# Puzzle_I2C_hub.net
KiCad netlist of a schematic drawn in EAGLE
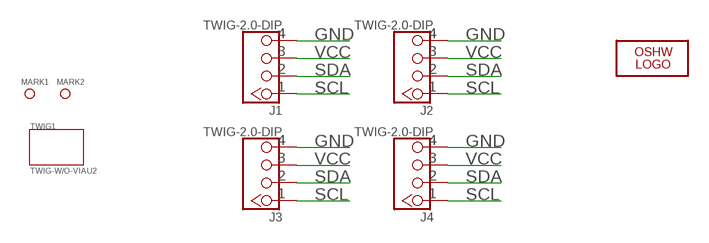
[diagram p0: schematic, sheet 1]

(export (version "E")
  (design (tool "Eeschema 10.0.6"))
  (components
    (comp (ref "J1")
      (value "TWIG-2.0-DIP")
      (footprint "eagle-import:2.0_1X4")
      (libsource (lib "eagle-import") (part "TWIG-2.0-DIP"))
    )
    (comp (ref "J2")
      (value "TWIG-2.0-DIP")
      (footprint "eagle-import:2.0_1X4")
      (libsource (lib "eagle-import") (part "TWIG-2.0-DIP"))
    )
    (comp (ref "J3")
      (value "TWIG-2.0-DIP")
      (footprint "eagle-import:2.0_1X4")
      (libsource (lib "eagle-import") (part "TWIG-2.0-DIP"))
    )
    (comp (ref "J4")
      (value "TWIG-2.0-DIP")
      (footprint "eagle-import:2.0_1X4")
      (libsource (lib "eagle-import") (part "TWIG-2.0-DIP"))
    )
    (comp (ref "LOGO3")
      (value "LOGO-OSHW-FILLX0150-NT")
      (footprint "eagle-import:OSHW_FILLX150_NOTEXT")
      (libsource (lib "eagle-import") (part "LOGO-OSHW-FILLX0150-NT"))
    )
    (comp (ref "MARK1")
      (value "PAD-MARK")
      (footprint "eagle-import:MARK")
      (libsource (lib "eagle-import") (part "PAD-MARK"))
    )
    (comp (ref "MARK2")
      (value "PAD-MARK")
      (footprint "eagle-import:MARK")
      (libsource (lib "eagle-import") (part "PAD-MARK"))
    )
    (comp (ref "TWIG1")
      (value "TWIG-W/O-VIAU2")
      (footprint "eagle-import:U2N")
      (libsource (lib "eagle-import") (part "TWIG-W/O-VIAU2"))
    )
  )
  (nets
    (net (code "1") (name "/GND") (class "Default")
      (node (ref "J1") (pin "4") (pinfunction "4_4") (pintype "bidirectional"))
      (node (ref "J2") (pin "4") (pinfunction "4_4") (pintype "bidirectional"))
      (node (ref "J3") (pin "4") (pinfunction "4_4") (pintype "bidirectional"))
      (node (ref "J4") (pin "4") (pinfunction "4_4") (pintype "bidirectional"))
    )
    (net (code "2") (name "/SCL") (class "Default")
      (node (ref "J1") (pin "1") (pinfunction "1_1") (pintype "bidirectional"))
      (node (ref "J2") (pin "1") (pinfunction "1_1") (pintype "bidirectional"))
      (node (ref "J3") (pin "1") (pinfunction "1_1") (pintype "bidirectional"))
      (node (ref "J4") (pin "1") (pinfunction "1_1") (pintype "bidirectional"))
    )
    (net (code "3") (name "/SDA") (class "Default")
      (node (ref "J1") (pin "2") (pinfunction "2_2") (pintype "bidirectional"))
      (node (ref "J2") (pin "2") (pinfunction "2_2") (pintype "bidirectional"))
      (node (ref "J3") (pin "2") (pinfunction "2_2") (pintype "bidirectional"))
      (node (ref "J4") (pin "2") (pinfunction "2_2") (pintype "bidirectional"))
    )
    (net (code "4") (name "/VCC") (class "Default")
      (node (ref "J1") (pin "3") (pinfunction "3_3") (pintype "bidirectional"))
      (node (ref "J2") (pin "3") (pinfunction "3_3") (pintype "bidirectional"))
      (node (ref "J3") (pin "3") (pinfunction "3_3") (pintype "bidirectional"))
      (node (ref "J4") (pin "3") (pinfunction "3_3") (pintype "bidirectional"))
    )
  )
)
